# SDram.net
KiCad netlist of a schematic drawn in Altium Designer
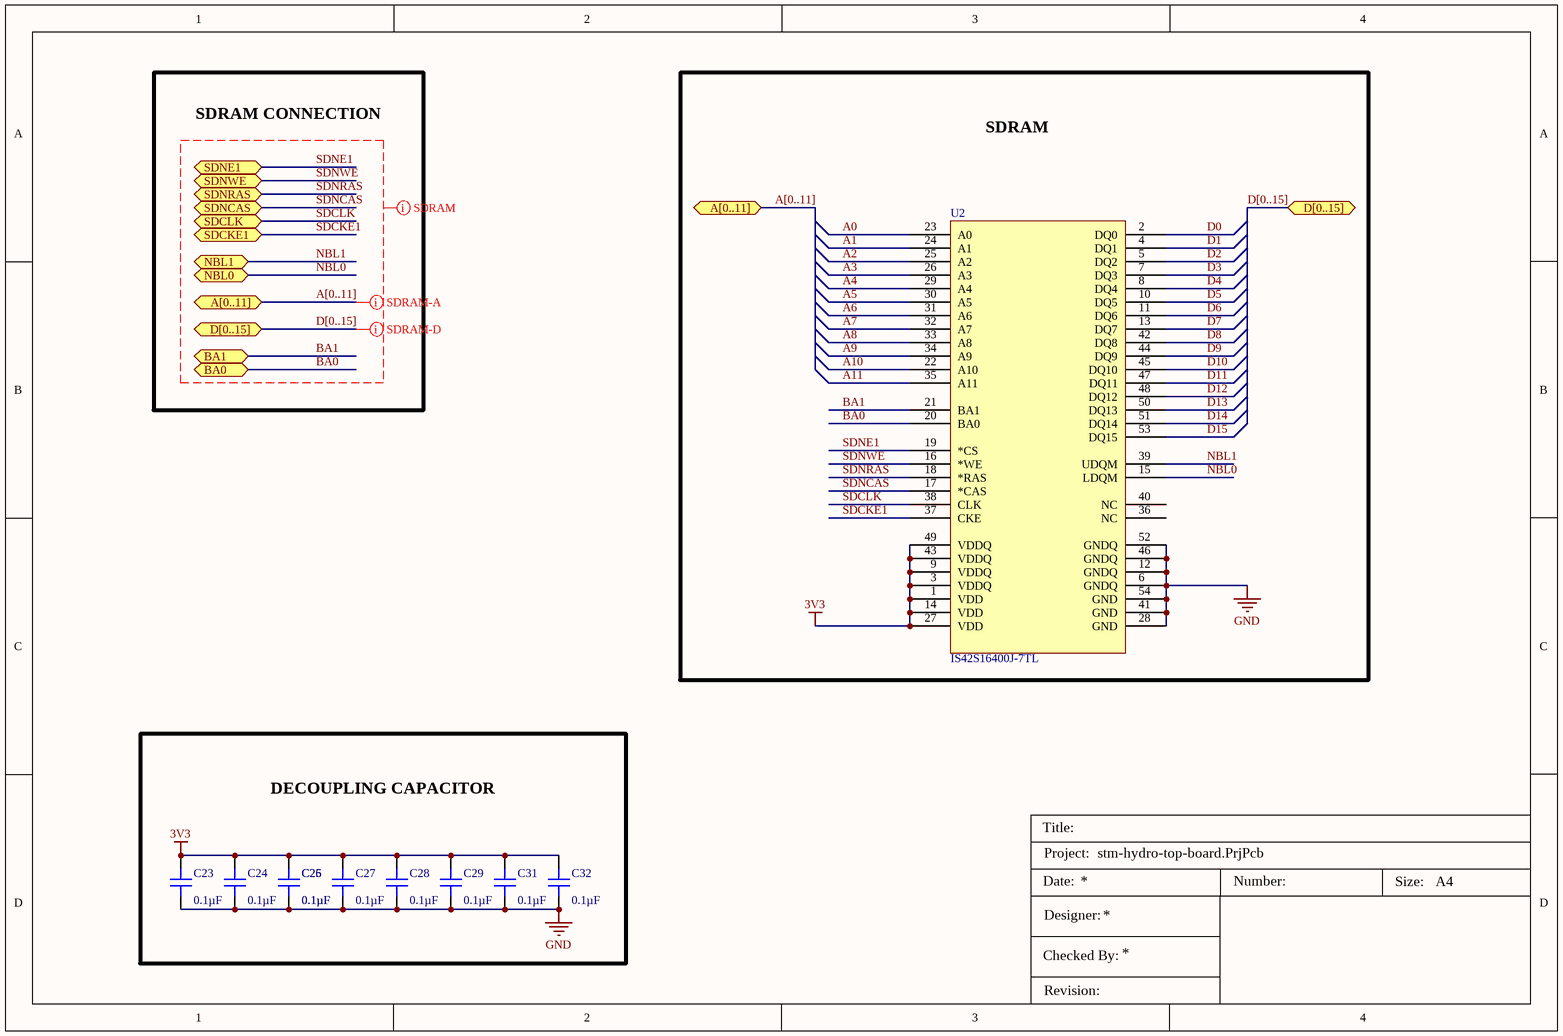
[diagram p0: SDram.SchDoc]

(export (version "E")
  (design (tool "Eeschema 10.0.6"))
  (components
    (comp (ref "C23")
      (value "0.1µF")
      (footprint "CAP 0603_1608")
      (description "CAP CER 0.1UF 6.3V X7R 0603")
      (fields (field (name "PART NUMBER") "6R3X14W104MV4T"))
      (libsource (lib "Celestial Altium Library - altium_library") (part "Capacitor"))
    )
    (comp (ref "C24")
      (value "0.1µF")
      (footprint "CAP 0603_1608")
      (description "CAP CER 0.1UF 6.3V X7R 0603")
      (fields (field (name "PART NUMBER") "6R3X14W104MV4T"))
      (libsource (lib "Celestial Altium Library - altium_library") (part "Capacitor"))
    )
    (comp (ref "C25")
      (value "0.1µF")
      (footprint "CAP 0603_1608")
      (description "CAP CER 0.1UF 6.3V X7R 0603")
      (fields (field (name "PART NUMBER") "6R3X14W104MV4T"))
      (libsource (lib "Celestial Altium Library - altium_library") (part "Capacitor"))
    )
    (comp (ref "C26")
      (value "0.1µF")
      (footprint "CAP 0603_1608")
      (description "CAP CER 0.1UF 6.3V X7R 0603")
      (fields (field (name "PART NUMBER") "6R3X14W104MV4T"))
      (libsource (lib "Celestial Altium Library - altium_library") (part "Capacitor"))
    )
    (comp (ref "C27")
      (value "0.1µF")
      (footprint "CAP 0603_1608")
      (description "CAP CER 0.1UF 6.3V X7R 0603")
      (fields (field (name "PART NUMBER") "6R3X14W104MV4T"))
      (libsource (lib "Celestial Altium Library - altium_library") (part "Capacitor"))
    )
    (comp (ref "C28")
      (value "0.1µF")
      (footprint "CAP 0603_1608")
      (description "CAP CER 0.1UF 6.3V X7R 0603")
      (fields (field (name "PART NUMBER") "6R3X14W104MV4T"))
      (libsource (lib "Celestial Altium Library - altium_library") (part "Capacitor"))
    )
    (comp (ref "C29")
      (value "0.1µF")
      (footprint "CAP 0603_1608")
      (description "CAP CER 0.1UF 6.3V X7R 0603")
      (fields (field (name "PART NUMBER") "6R3X14W104MV4T"))
      (libsource (lib "Celestial Altium Library - altium_library") (part "Capacitor"))
    )
    (comp (ref "C31")
      (value "0.1µF")
      (footprint "CAP 0603_1608")
      (description "CAP CER 0.1UF 6.3V X7R 0603")
      (fields (field (name "PART NUMBER") "6R3X14W104MV4T"))
      (libsource (lib "Celestial Altium Library - altium_library") (part "Capacitor"))
    )
    (comp (ref "C32")
      (value "0.1µF")
      (footprint "CAP 0603_1608")
      (description "CAP CER 0.1UF 6.3V X7R 0603")
      (fields (field (name "PART NUMBER") "6R3X14W104MV4T"))
      (libsource (lib "Celestial Altium Library - altium_library") (part "Capacitor"))
    )
    (comp (ref "U2")
      (value "IS42S16400J-7TL")
      (footprint "sdram")
      (description "No Description AvailablSDRAM Memory IC 64Mb (4M x 16) Parallel 143 MHz 5.4 ns 54-TSOP IIe")
      (fields (field (name "COPYRIGHT") "Copyright (C) 2018 Accelerated Designs. All rights reserved"))
      (libsource (lib "hy-smt") (part "IS42S16400J-7TL"))
    )
  )
  (nets
    (net (code "1") (name "/A0") (class "Default")
      (node (ref "U2") (pin "23") (pinfunction "A0_23") (pintype "passive"))
    )
    (net (code "2") (name "/A1") (class "Default")
      (node (ref "U2") (pin "24") (pinfunction "A1_24") (pintype "passive"))
    )
    (net (code "3") (name "/A2") (class "Default")
      (node (ref "U2") (pin "25") (pinfunction "A2_25") (pintype "passive"))
    )
    (net (code "4") (name "/A3") (class "Default")
      (node (ref "U2") (pin "26") (pinfunction "A3_26") (pintype "passive"))
    )
    (net (code "5") (name "/A4") (class "Default")
      (node (ref "U2") (pin "29") (pinfunction "A4_29") (pintype "passive"))
    )
    (net (code "6") (name "/A5") (class "Default")
      (node (ref "U2") (pin "30") (pinfunction "A5_30") (pintype "passive"))
    )
    (net (code "7") (name "/A6") (class "Default")
      (node (ref "U2") (pin "31") (pinfunction "A6_31") (pintype "passive"))
    )
    (net (code "8") (name "/A7") (class "Default")
      (node (ref "U2") (pin "32") (pinfunction "A7_32") (pintype "passive"))
    )
    (net (code "9") (name "/A8") (class "Default")
      (node (ref "U2") (pin "33") (pinfunction "A8_33") (pintype "passive"))
    )
    (net (code "10") (name "/A9") (class "Default")
      (node (ref "U2") (pin "34") (pinfunction "A9_34") (pintype "passive"))
    )
    (net (code "11") (name "/A10") (class "Default")
      (node (ref "U2") (pin "22") (pinfunction "A10_22") (pintype "passive"))
    )
    (net (code "12") (name "/A11") (class "Default")
      (node (ref "U2") (pin "35") (pinfunction "A11_35") (pintype "passive"))
    )
    (net (code "14") (name "/BA0") (class "Default")
      (node (ref "U2") (pin "20") (pinfunction "BA0_20") (pintype "passive"))
    )
    (net (code "15") (name "/BA1") (class "Default")
      (node (ref "U2") (pin "21") (pinfunction "BA1_21") (pintype "passive"))
    )
    (net (code "16") (name "/D0") (class "Default")
      (node (ref "U2") (pin "2") (pinfunction "DQ0_2") (pintype "passive"))
    )
    (net (code "17") (name "/D1") (class "Default")
      (node (ref "U2") (pin "4") (pinfunction "DQ1_4") (pintype "passive"))
    )
    (net (code "18") (name "/D2") (class "Default")
      (node (ref "U2") (pin "5") (pinfunction "DQ2_5") (pintype "passive"))
    )
    (net (code "19") (name "/D3") (class "Default")
      (node (ref "U2") (pin "7") (pinfunction "DQ3_7") (pintype "passive"))
    )
    (net (code "20") (name "/D4") (class "Default")
      (node (ref "U2") (pin "8") (pinfunction "DQ4_8") (pintype "passive"))
    )
    (net (code "21") (name "/D5") (class "Default")
      (node (ref "U2") (pin "10") (pinfunction "DQ5_10") (pintype "passive"))
    )
    (net (code "22") (name "/D6") (class "Default")
      (node (ref "U2") (pin "11") (pinfunction "DQ6_11") (pintype "passive"))
    )
    (net (code "23") (name "/D7") (class "Default")
      (node (ref "U2") (pin "13") (pinfunction "DQ7_13") (pintype "passive"))
    )
    (net (code "24") (name "/D8") (class "Default")
      (node (ref "U2") (pin "42") (pinfunction "DQ8_42") (pintype "passive"))
    )
    (net (code "25") (name "/D9") (class "Default")
      (node (ref "U2") (pin "44") (pinfunction "DQ9_44") (pintype "passive"))
    )
    (net (code "26") (name "/D10") (class "Default")
      (node (ref "U2") (pin "45") (pinfunction "DQ10_45") (pintype "passive"))
    )
    (net (code "27") (name "/D11") (class "Default")
      (node (ref "U2") (pin "47") (pinfunction "DQ11_47") (pintype "passive"))
    )
    (net (code "28") (name "/D12") (class "Default")
      (node (ref "U2") (pin "48") (pinfunction "DQ12_48") (pintype "passive"))
    )
    (net (code "29") (name "/D13") (class "Default")
      (node (ref "U2") (pin "50") (pinfunction "DQ13_50") (pintype "passive"))
    )
    (net (code "30") (name "/D14") (class "Default")
      (node (ref "U2") (pin "51") (pinfunction "DQ14_51") (pintype "passive"))
    )
    (net (code "31") (name "/D15") (class "Default")
      (node (ref "U2") (pin "53") (pinfunction "DQ15_53") (pintype "passive"))
    )
    (net (code "33") (name "/NBL0") (class "Default")
      (node (ref "U2") (pin "15") (pinfunction "LDQM_15") (pintype "passive"))
    )
    (net (code "34") (name "/NBL1") (class "Default")
      (node (ref "U2") (pin "39") (pinfunction "UDQM_39") (pintype "passive"))
    )
    (net (code "35") (name "/SDCKE1") (class "Default")
      (node (ref "U2") (pin "37") (pinfunction "CKE_37") (pintype "passive"))
    )
    (net (code "36") (name "/SDCLK") (class "Default")
      (node (ref "U2") (pin "38") (pinfunction "CLK_38") (pintype "passive"))
    )
    (net (code "37") (name "/SDNCAS") (class "Default")
      (node (ref "U2") (pin "17") (pinfunction "*CAS_17") (pintype "passive"))
    )
    (net (code "38") (name "/SDNE1") (class "Default")
      (node (ref "U2") (pin "19") (pinfunction "*CS_19") (pintype "passive"))
    )
    (net (code "39") (name "/SDNRAS") (class "Default")
      (node (ref "U2") (pin "18") (pinfunction "*RAS_18") (pintype "passive"))
    )
    (net (code "40") (name "/SDNWE") (class "Default")
      (node (ref "U2") (pin "16") (pinfunction "*WE_16") (pintype "passive"))
    )
    (net (code "41") (name "3V3") (class "Default")
      (node (ref "C23") (pin "2") (pinfunction "2_2") (pintype "passive"))
      (node (ref "C24") (pin "2") (pinfunction "2_2") (pintype "passive"))
      (node (ref "C25") (pin "2") (pinfunction "2_2") (pintype "passive"))
      (node (ref "C26") (pin "2") (pinfunction "2_2") (pintype "passive"))
      (node (ref "C27") (pin "2") (pinfunction "2_2") (pintype "passive"))
      (node (ref "C28") (pin "2") (pinfunction "2_2") (pintype "passive"))
      (node (ref "C29") (pin "2") (pinfunction "2_2") (pintype "passive"))
      (node (ref "C31") (pin "2") (pinfunction "2_2") (pintype "passive"))
      (node (ref "C32") (pin "2") (pinfunction "2_2") (pintype "passive"))
      (node (ref "U2") (pin "1") (pinfunction "VDD_1") (pintype "passive"))
      (node (ref "U2") (pin "14") (pinfunction "VDD_14") (pintype "passive"))
      (node (ref "U2") (pin "27") (pinfunction "VDD_27") (pintype "passive"))
      (node (ref "U2") (pin "3") (pinfunction "VDDQ_3") (pintype "passive"))
      (node (ref "U2") (pin "43") (pinfunction "VDDQ_43") (pintype "passive"))
      (node (ref "U2") (pin "49") (pinfunction "VDDQ_49") (pintype "passive"))
      (node (ref "U2") (pin "9") (pinfunction "VDDQ_9") (pintype "passive"))
    )
    (net (code "42") (name "GND") (class "Default")
      (node (ref "C23") (pin "1") (pinfunction "1_1") (pintype "passive"))
      (node (ref "C24") (pin "1") (pinfunction "1_1") (pintype "passive"))
      (node (ref "C25") (pin "1") (pinfunction "1_1") (pintype "passive"))
      (node (ref "C26") (pin "1") (pinfunction "1_1") (pintype "passive"))
      (node (ref "C27") (pin "1") (pinfunction "1_1") (pintype "passive"))
      (node (ref "C28") (pin "1") (pinfunction "1_1") (pintype "passive"))
      (node (ref "C29") (pin "1") (pinfunction "1_1") (pintype "passive"))
      (node (ref "C31") (pin "1") (pinfunction "1_1") (pintype "passive"))
      (node (ref "C32") (pin "1") (pinfunction "1_1") (pintype "passive"))
      (node (ref "U2") (pin "12") (pinfunction "GNDQ_12") (pintype "passive"))
      (node (ref "U2") (pin "28") (pinfunction "GND_28") (pintype "passive"))
      (node (ref "U2") (pin "41") (pinfunction "GND_41") (pintype "passive"))
      (node (ref "U2") (pin "46") (pinfunction "GNDQ_46") (pintype "passive"))
      (node (ref "U2") (pin "52") (pinfunction "GNDQ_52") (pintype "passive"))
      (node (ref "U2") (pin "54") (pinfunction "GND_54") (pintype "passive"))
      (node (ref "U2") (pin "6") (pinfunction "GNDQ_6") (pintype "passive"))
    )
    (net (code "43") (name "unconnected-(U2-NC-Pad36)") (class "Default")
      (node (ref "U2") (pin "36") (pinfunction "NC_36") (pintype "passive"))
    )
    (net (code "44") (name "unconnected-(U2-NC-Pad40)") (class "Default")
      (node (ref "U2") (pin "40") (pinfunction "NC_40") (pintype "passive"))
    )
  )
)
